# 24_Peripherals.net
KiCad netlist of a schematic drawn in Altium Designer
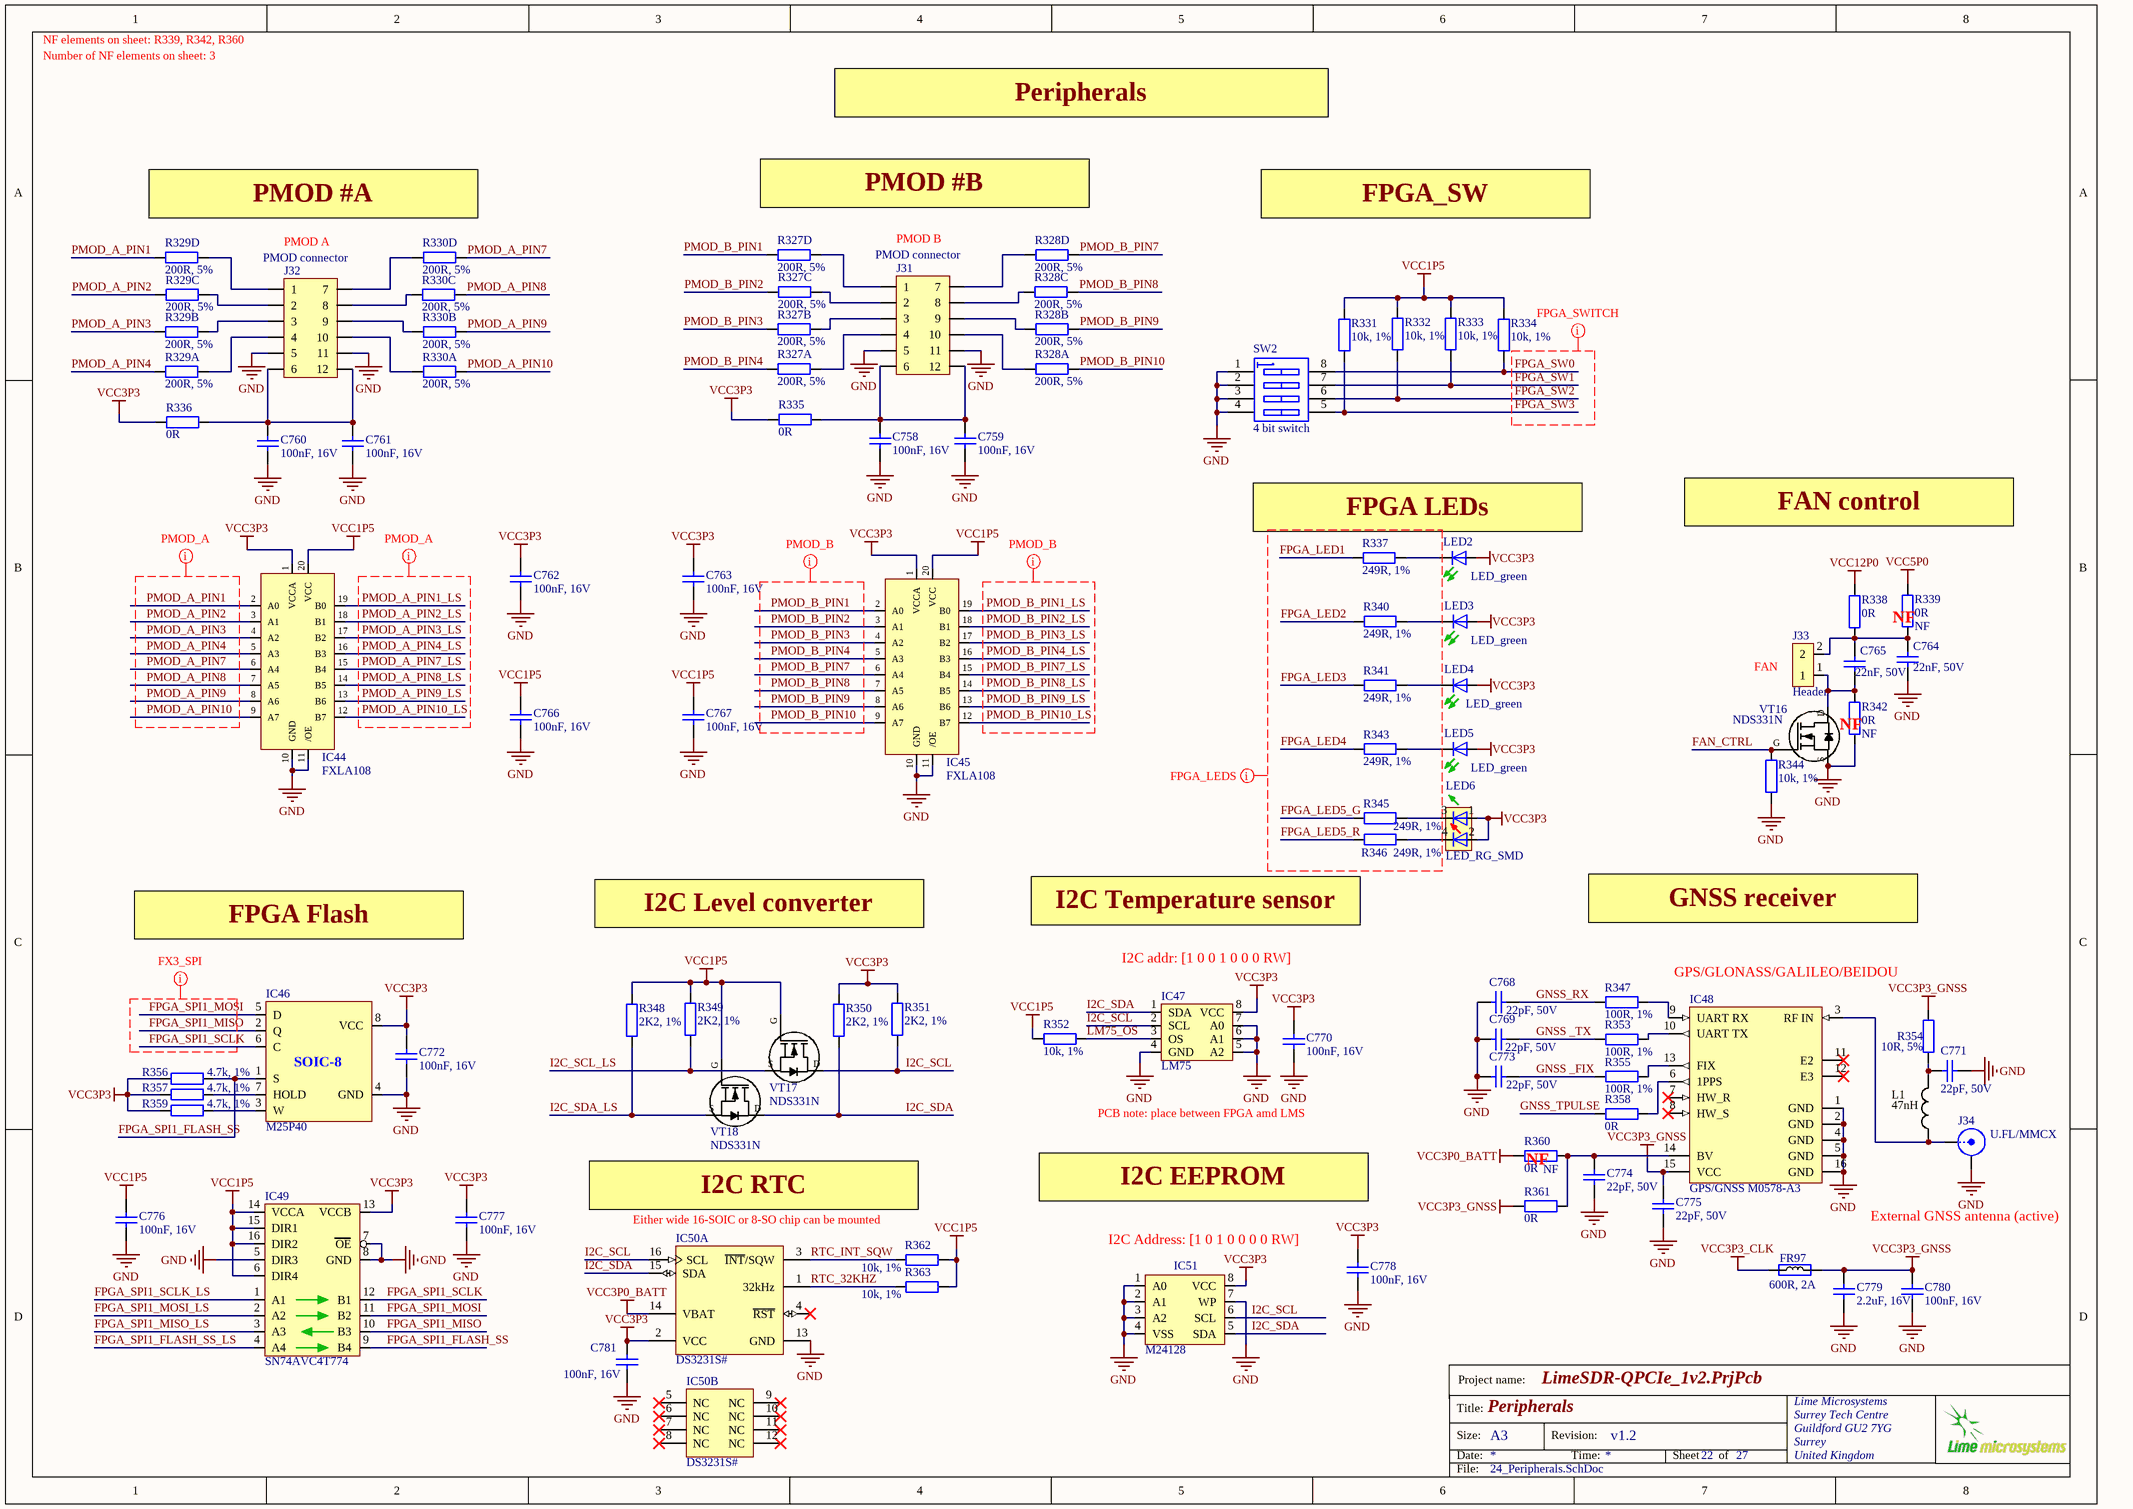
[diagram p0: 24_Peripherals.SchDoc]

(export (version "E")
  (design (tool "Eeschema 10.0.6"))
  (components
    (comp (ref "C758")
      (value "100nF, 16V")
      (footprint "CAP0402")
      (fields
        (field (name "TOLERANCE") "10 %")
        (field (name "MANUFACTURER") "Murata Electronics")
        (field (name "MANUFACTURER PART NUMBER") "GRM155R71C104KA88D")
      )
      (libsource (lib "LimeFPGAboard_schLib") (part "Cap_0603"))
    )
    (comp (ref "C759")
      (value "100nF, 16V")
      (footprint "CAP0402")
      (fields
        (field (name "TOLERANCE") "10 %")
        (field (name "MANUFACTURER") "Murata Electronics")
        (field (name "MANUFACTURER PART NUMBER") "GRM155R71C104KA88D")
      )
      (libsource (lib "LimeFPGAboard_schLib") (part "Cap_0603"))
    )
    (comp (ref "C760")
      (value "100nF, 16V")
      (footprint "CAP0402")
      (fields
        (field (name "TOLERANCE") "10 %")
        (field (name "MANUFACTURER") "Murata Electronics")
        (field (name "MANUFACTURER PART NUMBER") "GRM155R71C104KA88D")
      )
      (libsource (lib "LimeFPGAboard_schLib") (part "Cap_0603"))
    )
    (comp (ref "C761")
      (value "100nF, 16V")
      (footprint "CAP0402")
      (fields
        (field (name "TOLERANCE") "10 %")
        (field (name "MANUFACTURER") "Murata Electronics")
        (field (name "MANUFACTURER PART NUMBER") "GRM155R71C104KA88D")
      )
      (libsource (lib "LimeFPGAboard_schLib") (part "Cap_0603"))
    )
    (comp (ref "C762")
      (value "100nF, 16V")
      (footprint "CAP0402")
      (fields
        (field (name "TOLERANCE") "10 %")
        (field (name "MANUFACTURER") "Murata Electronics")
        (field (name "MANUFACTURER PART NUMBER") "GRM155R71C104KA88D")
      )
      (libsource (lib "LimeFPGAboard_schLib") (part "Cap_0603"))
    )
    (comp (ref "C763")
      (value "100nF, 16V")
      (footprint "CAP0402")
      (fields
        (field (name "TOLERANCE") "10 %")
        (field (name "MANUFACTURER") "Murata Electronics")
        (field (name "MANUFACTURER PART NUMBER") "GRM155R71C104KA88D")
      )
      (libsource (lib "LimeFPGAboard_schLib") (part "Cap_0603"))
    )
    (comp (ref "C764")
      (value "22nF, 50V")
      (footprint "CAP0402")
      (fields (field (name "TOLERANCE") "±10%") (field (name "MANUFACTURER") "Kemet"))
      (libsource (lib "LimeMicroAltiumLib_schLib") (part "Cap_0402"))
    )
    (comp (ref "C765")
      (value "22nF, 50V")
      (footprint "CAP0402")
      (fields (field (name "TOLERANCE") "±10%") (field (name "MANUFACTURER") "Kemet"))
      (libsource (lib "LimeMicroAltiumLib_schLib") (part "Cap_0402"))
    )
    (comp (ref "C766")
      (value "100nF, 16V")
      (footprint "CAP0402")
      (fields
        (field (name "TOLERANCE") "10 %")
        (field (name "MANUFACTURER") "Murata Electronics")
        (field (name "MANUFACTURER PART NUMBER") "GRM155R71C104KA88D")
      )
      (libsource (lib "LimeFPGAboard_schLib") (part "Cap_0603"))
    )
    (comp (ref "C767")
      (value "100nF, 16V")
      (footprint "CAP0402")
      (fields
        (field (name "TOLERANCE") "10 %")
        (field (name "MANUFACTURER") "Murata Electronics")
        (field (name "MANUFACTURER PART NUMBER") "GRM155R71C104KA88D")
      )
      (libsource (lib "LimeFPGAboard_schLib") (part "Cap_0603"))
    )
    (comp (ref "C768")
      (value "22pF, 50V")
      (footprint "CAP0402")
      (fields (field (name "TOLERANCE") "±5%") (field (name "MANUFACTURER") "Yageo"))
      (libsource (lib "LimeMicroAltiumLib_schLib") (part "Cap_0402"))
    )
    (comp (ref "C769")
      (value "22pF, 50V")
      (footprint "CAP0402")
      (fields (field (name "TOLERANCE") "±5%") (field (name "MANUFACTURER") "Yageo"))
      (libsource (lib "LimeMicroAltiumLib_schLib") (part "Cap_0402"))
    )
    (comp (ref "C770")
      (value "100nF, 16V")
      (footprint "CAP0402")
      (fields
        (field (name "TOLERANCE") "10 %")
        (field (name "MANUFACTURER") "Murata Electronics")
        (field (name "MANUFACTURER PART NUMBER") "GRM155R71C104KA88D")
      )
      (libsource (lib "LimeFPGAboard_schLib") (part "Cap_0603"))
    )
    (comp (ref "C771")
      (value "22pF, 50V")
      (footprint "CAP0402")
      (fields (field (name "TOLERANCE") "±5%") (field (name "MANUFACTURER") "Yageo"))
      (libsource (lib "LimeMicroAltiumLib_schLib") (part "Cap_0402"))
    )
    (comp (ref "C772")
      (value "100nF, 16V")
      (footprint "CAP0402")
      (fields
        (field (name "TOLERANCE") "10 %")
        (field (name "MANUFACTURER") "Murata Electronics")
        (field (name "MANUFACTURER PART NUMBER") "GRM155R71C104KA88D")
      )
      (libsource (lib "LimeFPGAboard_schLib") (part "Cap_0603"))
    )
    (comp (ref "C773")
      (value "22pF, 50V")
      (footprint "CAP0402")
      (fields (field (name "TOLERANCE") "±5%") (field (name "MANUFACTURER") "Yageo"))
      (libsource (lib "LimeMicroAltiumLib_schLib") (part "Cap_0402"))
    )
    (comp (ref "C774")
      (value "22pF, 50V")
      (footprint "CAP0402")
      (fields (field (name "TOLERANCE") "±5%") (field (name "MANUFACTURER") "Yageo"))
      (libsource (lib "LimeMicroAltiumLib_schLib") (part "Cap_0402"))
    )
    (comp (ref "C775")
      (value "22pF, 50V")
      (footprint "CAP0402")
      (fields (field (name "TOLERANCE") "±5%") (field (name "MANUFACTURER") "Yageo"))
      (libsource (lib "LimeMicroAltiumLib_schLib") (part "Cap_0402"))
    )
    (comp (ref "C776")
      (value "100nF, 16V")
      (footprint "CAP0402")
      (fields
        (field (name "TOLERANCE") "10 %")
        (field (name "MANUFACTURER") "Murata Electronics")
        (field (name "MANUFACTURER PART NUMBER") "GRM155R71C104KA88D")
      )
      (libsource (lib "LimeFPGAboard_schLib") (part "Cap_0603"))
    )
    (comp (ref "C777")
      (value "100nF, 16V")
      (footprint "CAP0402")
      (fields
        (field (name "TOLERANCE") "10 %")
        (field (name "MANUFACTURER") "Murata Electronics")
        (field (name "MANUFACTURER PART NUMBER") "GRM155R71C104KA88D")
      )
      (libsource (lib "LimeFPGAboard_schLib") (part "Cap_0603"))
    )
    (comp (ref "C778")
      (value "100nF, 16V")
      (footprint "CAP0402")
      (fields
        (field (name "TOLERANCE") "10 %")
        (field (name "MANUFACTURER") "Murata Electronics")
        (field (name "MANUFACTURER PART NUMBER") "GRM155R71C104KA88D")
      )
      (libsource (lib "LimeFPGAboard_schLib") (part "Cap_0603"))
    )
    (comp (ref "C779")
      (value "2.2uF, 16V")
      (footprint "CAP0402")
      (description "CAP CER 2.2UF 16V 10% X5R 0402")
      (fields (field (name "MANUFACTURER") "TDK Corporation") (field (name "TOLERANCE") "±20%"))
      (libsource (lib "LimeMicroAltiumLib_schLib") (part "Cap_0402"))
    )
    (comp (ref "C780")
      (value "100nF, 16V")
      (footprint "CAP0402")
      (fields
        (field (name "MANUFACTURER") "Murata Electronics")
        (field (name "TOLERANCE") "10 %")
        (field (name "MANUFACTURER PART NUMBER") "GRM155R71C104KA88D")
      )
      (libsource (lib "LimeMicroAltiumLib_schLib") (part "Cap_0402"))
    )
    (comp (ref "C781")
      (value "100nF, 16V")
      (footprint "CAP0402")
      (fields
        (field (name "MANUFACTURER") "Murata Electronics")
        (field (name "TOLERANCE") "10 %")
        (field (name "MANUFACTURER PART NUMBER") "GRM155R71C104KA88D")
      )
      (libsource (lib "LimeMicroAltiumLib_schLib") (part "Cap_0402"))
    )
    (comp (ref "FR97")
      (value "600R, 2A")
      (footprint "RES0805")
      (fields (field (name "MANUFACTURER") "TDK"))
      (libsource (lib "LimeMicroAltiumLib_schLib") (part "Ferrite"))
    )
    (comp (ref "IC44")
      (value "FXLA108")
      (footprint "FXLA108")
      (fields (field (name "MANUFACTURER") "Fairchild Semiconductor"))
      (libsource (lib "LimeFPGAboard_schLib") (part "FXLA108"))
    )
    (comp (ref "IC45")
      (value "FXLA108")
      (footprint "FXLA108")
      (fields (field (name "MANUFACTURER") "Fairchild Semiconductor"))
      (libsource (lib "LimeFPGAboard_schLib") (part "FXLA108"))
    )
    (comp (ref "IC46")
      (value "M25P40")
      (footprint "M25P40-VMN6TPB_SO8N")
      (fields (field (name "MANUFACTURER") "Micron Technology Inc"))
      (libsource (lib "LimeFPGAboard_schLib") (part "M25P40"))
    )
    (comp (ref "IC47")
      (value "LM75")
      (footprint "HWSON8_LM75")
      (fields
        (field (name "MANUFACTURER") "NXP Semiconductors")
        (field (name "MANUFACTURER PART NUMBER") "LM75BTP,147")
      )
      (libsource (lib "LimeMicroAltiumLib_schLib") (part "LM75"))
    )
    (comp (ref "IC48")
      (value "GPS/GNSS M0578-A3")
      (footprint "M10578-A3")
      (fields (field (name "MANUFACTURER") "Antenova"))
      (libsource (lib "LimeMicroAltiumLib_schLib") (part "M10578-A3_GPS_GNSS"))
    )
    (comp (ref "IC49")
      (value "SN74AVC4T774")
      (footprint "SN74AVC4T774")
      (fields (field (name "MANUFACTURER") "Texas Instruments"))
      (libsource (lib "LimeMicroAltiumLib_schLib") (part "SN74AVC4T774"))
    )
    (comp (ref "IC50")
      (value "DS3231S#")
      (footprint "DS3231S#_SOIC16_SOIC8")
      (fields (field (name "MANUFACTURER") "MAXIM INTEGRATED PRODUCTS"))
      (libsource (lib "LimeMicroAltiumLib_schLib") (part "DS3231S#"))
    )
    (comp (ref "IC51")
      (value "M24128")
      (footprint "24FC512")
      (fields (field (name "MANUFACTURER") "STMicroelectronics"))
      (libsource (lib "LimeMicroAltiumLib_schLib") (part "24FC64F"))
    )
    (comp (ref "J31")
      (value "PMOD connector")
      (footprint "PMODconn_right_angle_TH")
      (description "Header, 4-Pin, Dual row")
      (fields (field (name "MANUFACTURER") "Sullins Connector Solutions"))
      (libsource (lib "LimeMicroAltiumLib_schLib") (part "PMOD_connector"))
    )
    (comp (ref "J32")
      (value "PMOD connector")
      (footprint "PMODconn_right_angle_TH")
      (description "Header, 4-Pin, Dual row")
      (fields (field (name "MANUFACTURER") "Sullins Connector Solutions"))
      (libsource (lib "LimeMicroAltiumLib_schLib") (part "PMOD_connector"))
    )
    (comp (ref "J33")
      (value "Header")
      (footprint "HDR_1x2")
      (fields (field (name "MANUFACTURER") "3M"))
      (libsource (lib "LimeFPGAboard_schLib") (part "Jumper"))
    )
    (comp (ref "J34")
      (value "U.FL/MMCX")
      (footprint "MMCX_UFL_conn_u")
      (description "CONN UMC RCPT STR 50 OHM SMD")
      (fields (field (name "MANUFACTURER") "Molex, LLC"))
      (libsource (lib "LimeMicroAltiumLib_schLib") (part "RF_IF_connector"))
    )
    (comp (ref "L1")
      (value "47nH")
      (footprint "RES0402")
      (fields
        (field (name "MANUFACTURER") "COILCRAFT")
        (field (name "MANUFACTURER PART NUMBER") "0402HP-47NXJLU")
      )
      (libsource (lib "LimeMicroAltiumLib_schLib") (part "Inductor_0603"))
    )
    (comp (ref "LED2")
      (value "LED_green")
      (footprint "LED-0603-GREEN")
      (fields
        (field (name "MANUFACTURER") "Avago Technologies US Inc.")
        (field (name "MANUFACTURER_1") "Broadcom Limited")
      )
      (libsource (lib "LimeMicroAltiumLib_schLib") (part "LED_green"))
    )
    (comp (ref "LED3")
      (value "LED_green")
      (footprint "LED-0603-GREEN")
      (fields
        (field (name "MANUFACTURER") "Avago Technologies US Inc.")
        (field (name "MANUFACTURER_1") "Broadcom Limited")
      )
      (libsource (lib "LimeMicroAltiumLib_schLib") (part "LED_green"))
    )
    (comp (ref "LED4")
      (value "LED_green")
      (footprint "LED-0603-GREEN")
      (fields
        (field (name "MANUFACTURER") "Avago Technologies US Inc.")
        (field (name "MANUFACTURER_1") "Broadcom Limited")
      )
      (libsource (lib "LimeMicroAltiumLib_schLib") (part "LED_green"))
    )
    (comp (ref "LED5")
      (value "LED_green")
      (footprint "LED-0603-GREEN")
      (fields
        (field (name "MANUFACTURER") "Avago Technologies US Inc.")
        (field (name "MANUFACTURER_1") "Broadcom Limited")
      )
      (libsource (lib "LimeMicroAltiumLib_schLib") (part "LED_green"))
    )
    (comp (ref "LED6")
      (value "LED_RG_SMD")
      (footprint "LED-2x0603")
      (fields (field (name "MANUFACTURER") "Avago Technologies US Inc."))
      (libsource (lib "LimeMicroAltiumLib_schLib") (part "LED_green_red_SMD"))
    )
    (comp (ref "R327")
      (value "200R, 5%")
      (footprint "ChipResistorArray")
      (fields (field (name "MANUFACTURER") "Vishay Dale") (field (name "TOLERANCE") "±5%"))
      (libsource (lib "altium-import") (part "root_0_ResArray_0802_"))
    )
    (comp (ref "R328")
      (value "200R, 5%")
      (footprint "ChipResistorArray")
      (fields (field (name "MANUFACTURER") "Vishay Dale") (field (name "TOLERANCE") "±5%"))
      (libsource (lib "altium-import") (part "root_0_mirrored_ResArray_0802_"))
    )
    (comp (ref "R329")
      (value "200R, 5%")
      (footprint "ChipResistorArray")
      (fields (field (name "MANUFACTURER") "Vishay Dale") (field (name "TOLERANCE") "±5%"))
      (libsource (lib "altium-import") (part "root_0_ResArray_0802_"))
    )
    (comp (ref "R330")
      (value "200R, 5%")
      (footprint "ChipResistorArray")
      (fields (field (name "MANUFACTURER") "Vishay Dale") (field (name "TOLERANCE") "±5%"))
      (libsource (lib "altium-import") (part "root_0_mirrored_ResArray_0802_"))
    )
    (comp (ref "R331")
      (value "10k, 1%")
      (footprint "RES0402")
      (fields (field (name "MANUFACTURER") "Yageo") (field (name "TOLERANCE") "±1%"))
      (libsource (lib "LimeMicroAltiumLib_schLib") (part "Res_0402"))
    )
    (comp (ref "R332")
      (value "10k, 1%")
      (footprint "RES0402")
      (fields (field (name "MANUFACTURER") "Yageo") (field (name "TOLERANCE") "±1%"))
      (libsource (lib "LimeMicroAltiumLib_schLib") (part "Res_0402"))
    )
    (comp (ref "R333")
      (value "10k, 1%")
      (footprint "RES0402")
      (fields (field (name "MANUFACTURER") "Yageo") (field (name "TOLERANCE") "±1%"))
      (libsource (lib "LimeMicroAltiumLib_schLib") (part "Res_0402"))
    )
    (comp (ref "R334")
      (value "10k, 1%")
      (footprint "RES0402")
      (fields (field (name "MANUFACTURER") "Yageo") (field (name "TOLERANCE") "±1%"))
      (libsource (lib "LimeMicroAltiumLib_schLib") (part "Res_0402"))
    )
    (comp (ref "R335")
      (value "0R")
      (footprint "RES0402")
      (fields (field (name "MANUFACTURER") "Yageo") (field (name "TOLERANCE") "Jumper"))
      (libsource (lib "LimeMicroAltiumLib_schLib") (part "Res_0402"))
    )
    (comp (ref "R336")
      (value "0R")
      (footprint "RES0402")
      (fields (field (name "MANUFACTURER") "Yageo") (field (name "TOLERANCE") "Jumper"))
      (libsource (lib "LimeMicroAltiumLib_schLib") (part "Res_0402"))
    )
    (comp (ref "R337")
      (value "249R, 1%")
      (footprint "RES0402")
      (fields (field (name "MANUFACTURER") "Stackpole Electronics Inc") (field (name "TOLERANCE") "±1%"))
      (libsource (lib "LimeMicroAltiumLib_schLib") (part "Res_0402"))
    )
    (comp (ref "R338")
      (value "0R")
      (footprint "RES0402")
      (fields (field (name "MANUFACTURER") "Yageo") (field (name "TOLERANCE") "Jumper"))
      (libsource (lib "LimeMicroAltiumLib_schLib") (part "Res_0402"))
    )
    (comp (ref "R339")
      (value "0R")
      (footprint "RES0402")
      (fields
        (field (name "ASSEMBLY INFO") "NF")
        (field (name "MANUFACTURER") "Yageo")
        (field (name "TOLERANCE") "Jumper")
      )
      (libsource (lib "LimeMicroAltiumLib_schLib") (part "Res_0402"))
    )
    (comp (ref "R340")
      (value "249R, 1%")
      (footprint "RES0402")
      (fields (field (name "MANUFACTURER") "Stackpole Electronics Inc") (field (name "TOLERANCE") "±1%"))
      (libsource (lib "LimeMicroAltiumLib_schLib") (part "Res_0402"))
    )
    (comp (ref "R341")
      (value "249R, 1%")
      (footprint "RES0402")
      (fields (field (name "MANUFACTURER") "Stackpole Electronics Inc") (field (name "TOLERANCE") "±1%"))
      (libsource (lib "LimeMicroAltiumLib_schLib") (part "Res_0402"))
    )
    (comp (ref "R342")
      (value "0R")
      (footprint "RES0402")
      (fields
        (field (name "ASSEMBLY INFO") "NF")
        (field (name "MANUFACTURER") "Yageo")
        (field (name "TOLERANCE") "Jumper")
      )
      (libsource (lib "LimeMicroAltiumLib_schLib") (part "Res_0402"))
    )
    (comp (ref "R343")
      (value "249R, 1%")
      (footprint "RES0402")
      (fields (field (name "MANUFACTURER") "Stackpole Electronics Inc") (field (name "TOLERANCE") "±1%"))
      (libsource (lib "LimeMicroAltiumLib_schLib") (part "Res_0402"))
    )
    (comp (ref "R344")
      (value "10k, 1%")
      (footprint "RES0402")
      (fields (field (name "MANUFACTURER") "Yageo") (field (name "TOLERANCE") "±1%"))
      (libsource (lib "LimeMicroAltiumLib_schLib") (part "Res_0402"))
    )
    (comp (ref "R345")
      (value "249R, 1%")
      (footprint "RES0402")
      (fields (field (name "MANUFACTURER") "Stackpole Electronics Inc") (field (name "TOLERANCE") "±1%"))
      (libsource (lib "LimeMicroAltiumLib_schLib") (part "Res_0402"))
    )
    (comp (ref "R346")
      (value "249R, 1%")
      (footprint "RES0402")
      (fields (field (name "MANUFACTURER") "Stackpole Electronics Inc") (field (name "TOLERANCE") "±1%"))
      (libsource (lib "LimeMicroAltiumLib_schLib") (part "Res_0402"))
    )
    (comp (ref "R347")
      (value "100R, 1%")
      (footprint "RES0402")
      (fields (field (name "TOLERANCE") "±1%") (field (name "MANUFACTURER") "Stackpole Electronics Inc."))
      (libsource (lib "LimeFPGAboard_schLib") (part "Res_0402"))
    )
    (comp (ref "R348")
      (value "2K2, 1%")
      (footprint "RES0402")
      (fields (field (name "TOLERANCE") "±1%"))
      (libsource (lib "LimeFPGAboard_schLib") (part "Res_0402"))
    )
    (comp (ref "R349")
      (value "2K2, 1%")
      (footprint "RES0402")
      (fields (field (name "TOLERANCE") "±1%"))
      (libsource (lib "LimeFPGAboard_schLib") (part "Res_0402"))
    )
    (comp (ref "R350")
      (value "2K2, 1%")
      (footprint "RES0402")
      (fields (field (name "TOLERANCE") "±1%"))
      (libsource (lib "LimeFPGAboard_schLib") (part "Res_0402"))
    )
    (comp (ref "R351")
      (value "2K2, 1%")
      (footprint "RES0402")
      (fields (field (name "TOLERANCE") "±1%"))
      (libsource (lib "LimeFPGAboard_schLib") (part "Res_0402"))
    )
    (comp (ref "R352")
      (value "10k, 1%")
      (footprint "RES0402")
      (fields (field (name "MANUFACTURER") "Yageo") (field (name "TOLERANCE") "±1%"))
      (libsource (lib "LimeMicroAltiumLib_schLib") (part "Res_0402"))
    )
    (comp (ref "R353")
      (value "100R, 1%")
      (footprint "RES0402")
      (fields (field (name "TOLERANCE") "±1%") (field (name "MANUFACTURER") "Stackpole Electronics Inc."))
      (libsource (lib "LimeFPGAboard_schLib") (part "Res_0402"))
    )
    (comp (ref "R354")
      (value "10R, 5%")
      (footprint "RES0402")
      (fields (field (name "TOLERANCE") "±5%") (field (name "MANUFACTURER") "Yageo"))
      (libsource (lib "LimeMicroAltiumLib_schLib") (part "Res_0402"))
    )
    (comp (ref "R355")
      (value "100R, 1%")
      (footprint "RES0402")
      (fields (field (name "TOLERANCE") "±1%") (field (name "MANUFACTURER") "Stackpole Electronics Inc."))
      (libsource (lib "LimeFPGAboard_schLib") (part "Res_0402"))
    )
    (comp (ref "R356")
      (value "4.7k, 1%")
      (footprint "RES0402")
      (fields (field (name "MANUFACTURER") "Yageo") (field (name "TOLERANCE") "±1%"))
      (libsource (lib "LimeMicroAltiumLib_schLib") (part "Res_0402"))
    )
    (comp (ref "R357")
      (value "4.7k, 1%")
      (footprint "RES0402")
      (fields (field (name "MANUFACTURER") "Yageo") (field (name "TOLERANCE") "±1%"))
      (libsource (lib "LimeMicroAltiumLib_schLib") (part "Res_0402"))
    )
    (comp (ref "R358")
      (value "0R")
      (footprint "RES0402")
      (fields (field (name "MANUFACTURER") "Yageo") (field (name "TOLERANCE") "Jumper"))
      (libsource (lib "LimeMicroAltiumLib_schLib") (part "Res_0402"))
    )
    (comp (ref "R359")
      (value "4.7k, 1%")
      (footprint "RES0402")
      (fields (field (name "MANUFACTURER") "Yageo") (field (name "TOLERANCE") "±1%"))
      (libsource (lib "LimeMicroAltiumLib_schLib") (part "Res_0402"))
    )
    (comp (ref "R360")
      (value "0R")
      (footprint "RES0402_v2")
      (fields
        (field (name "ASSEMBLY INFO") "NF")
        (field (name "MANUFACTURER") "Yageo")
        (field (name "TOLERANCE") "Jumper")
      )
      (libsource (lib "LimeMicroAltiumLib_schLib") (part "Res_0402"))
    )
    (comp (ref "R361")
      (value "0R")
      (footprint "RES0402")
      (fields (field (name "MANUFACTURER") "Yageo") (field (name "TOLERANCE") "Jumper"))
      (libsource (lib "LimeMicroAltiumLib_schLib") (part "Res_0402"))
    )
    (comp (ref "R362")
      (value "10k, 1%")
      (footprint "RES0402")
      (fields (field (name "MANUFACTURER") "Yageo") (field (name "TOLERANCE") "±1%"))
      (libsource (lib "LimeMicroAltiumLib_schLib") (part "Res_0402"))
    )
    (comp (ref "R363")
      (value "10k, 1%")
      (footprint "RES0402")
      (fields (field (name "MANUFACTURER") "Yageo") (field (name "TOLERANCE") "±1%"))
      (libsource (lib "LimeMicroAltiumLib_schLib") (part "Res_0402"))
    )
    (comp (ref "SW2")
      (value "4 bit switch")
      (footprint "SW_4WAY_SMD_1P27")
      (fields (field (name "MANUFACTURER") "Omron Electronics Inc-EMC Div"))
      (libsource (lib "LimeMicroAltiumLib_schLib") (part "SW_SM_4bit"))
    )
    (comp (ref "VT16")
      (value "NDS331N")
      (footprint "SOT23-3")
      (fields (field (name "MANUFACTURER") "Fairchild Semiconductor"))
      (libsource (lib "LimeFPGAboard_schLib") (part "NDS331N"))
    )
    (comp (ref "VT17")
      (value "NDS331N")
      (footprint "SOT23-3")
      (fields (field (name "MANUFACTURER") "Fairchild Semiconductor"))
      (libsource (lib "LimeFPGAboard_schLib") (part "NDS331N"))
    )
    (comp (ref "VT18")
      (value "NDS331N")
      (footprint "SOT23-3")
      (fields (field (name "MANUFACTURER") "Fairchild Semiconductor"))
      (libsource (lib "LimeFPGAboard_schLib") (part "NDS331N"))
    )
  )
  (nets
    (net (code "1") (name "/FAN_CTRL") (class "Default")
      (node (ref "R344") (pin "1") (pinfunction "1_1") (pintype "passive"))
      (node (ref "VT16") (pin "G") (pinfunction "G_G") (pintype "passive"))
    )
    (net (code "2") (name "/FPGA_LED1") (class "Default")
      (node (ref "R337") (pin "1") (pinfunction "1_1") (pintype "passive"))
    )
    (net (code "3") (name "/FPGA_LED2") (class "Default")
      (node (ref "R340") (pin "1") (pinfunction "1_1") (pintype "passive"))
    )
    (net (code "4") (name "/FPGA_LED3") (class "Default")
      (node (ref "R341") (pin "1") (pinfunction "1_1") (pintype "passive"))
    )
    (net (code "5") (name "/FPGA_LED4") (class "Default")
      (node (ref "R343") (pin "1") (pinfunction "1_1") (pintype "passive"))
    )
    (net (code "6") (name "/FPGA_LED5_G") (class "Default")
      (node (ref "R345") (pin "1") (pinfunction "1_1") (pintype "passive"))
    )
    (net (code "7") (name "/FPGA_LED5_R") (class "Default")
      (node (ref "R346") (pin "1") (pinfunction "1_1") (pintype "passive"))
    )
    (net (code "8") (name "/FPGA_SPI1_FLASH_SS") (class "Default")
      (node (ref "IC46") (pin "1") (pinfunction "S_1") (pintype "passive"))
      (node (ref "IC49") (pin "9") (pinfunction "B4_9") (pintype "passive"))
      (node (ref "R356") (pin "1") (pinfunction "1_1") (pintype "passive"))
    )
    (net (code "9") (name "/FPGA_SPI1_FLASH_SS_LS") (class "Default")
      (node (ref "IC49") (pin "4") (pinfunction "A4_4") (pintype "passive"))
    )
    (net (code "10") (name "/FPGA_SPI1_MISO") (class "Default")
      (node (ref "IC46") (pin "2") (pinfunction "Q_2") (pintype "passive"))
      (node (ref "IC49") (pin "10") (pinfunction "B3_10") (pintype "passive"))
    )
    (net (code "11") (name "/FPGA_SPI1_MISO_LS") (class "Default")
      (node (ref "IC49") (pin "3") (pinfunction "A3_3") (pintype "passive"))
    )
    (net (code "12") (name "/FPGA_SPI1_MOSI") (class "Default")
      (node (ref "IC46") (pin "5") (pinfunction "D_5") (pintype "passive"))
      (node (ref "IC49") (pin "11") (pinfunction "B2_11") (pintype "passive"))
    )
    (net (code "13") (name "/FPGA_SPI1_MOSI_LS") (class "Default")
      (node (ref "IC49") (pin "2") (pinfunction "A2_2") (pintype "passive"))
    )
    (net (code "14") (name "/FPGA_SPI1_SCLK") (class "Default")
      (node (ref "IC46") (pin "6") (pinfunction "C_6") (pintype "passive"))
      (node (ref "IC49") (pin "12") (pinfunction "B1_12") (pintype "passive"))
    )
    (net (code "15") (name "/FPGA_SPI1_SCLK_LS") (class "Default")
      (node (ref "IC49") (pin "1") (pinfunction "A1_1") (pintype "passive"))
    )
    (net (code "16") (name "/FPGA_SW0") (class "Default")
      (node (ref "R334") (pin "2") (pinfunction "2_2") (pintype "passive"))
      (node (ref "SW2") (pin "8") (pinfunction "B1_8") (pintype "passive"))
    )
    (net (code "17") (name "/FPGA_SW1") (class "Default")
      (node (ref "R333") (pin "2") (pinfunction "2_2") (pintype "passive"))
      (node (ref "SW2") (pin "7") (pinfunction "B2_7") (pintype "passive"))
    )
    (net (code "18") (name "/FPGA_SW2") (class "Default")
      (node (ref "R332") (pin "2") (pinfunction "2_2") (pintype "passive"))
      (node (ref "SW2") (pin "6") (pinfunction "B3_6") (pintype "passive"))
    )
    (net (code "19") (name "/FPGA_SW3") (class "Default")
      (node (ref "R331") (pin "2") (pinfunction "2_2") (pintype "passive"))
      (node (ref "SW2") (pin "5") (pinfunction "B4_5") (pintype "passive"))
    )
    (net (code "20") (name "/GNSS _FIX") (class "Default")
      (node (ref "C773") (pin "1") (pinfunction "1_1") (pintype "passive"))
      (node (ref "R355") (pin "2") (pinfunction "2_2") (pintype "passive"))
    )
    (net (code "21") (name "/GNSS _TX") (class "Default")
      (node (ref "C769") (pin "1") (pinfunction "1_1") (pintype "passive"))
      (node (ref "R353") (pin "2") (pinfunction "2_2") (pintype "passive"))
    )
    (net (code "22") (name "/GNSS_RX") (class "Default")
      (node (ref "C768") (pin "1") (pinfunction "1_1") (pintype "passive"))
      (node (ref "R347") (pin "2") (pinfunction "2_2") (pintype "passive"))
    )
    (net (code "23") (name "/GNSS_TPULSE") (class "Default")
      (node (ref "R358") (pin "2") (pinfunction "2_2") (pintype "passive"))
    )
    (net (code "24") (name "/I2C_SCL") (class "Default")
      (node (ref "IC47") (pin "2") (pinfunction "SCL_2") (pintype "passive"))
      (node (ref "IC50") (pin "16") (pinfunction "SCL_16") (pintype "input"))
      (node (ref "IC51") (pin "6") (pinfunction "SCL_6") (pintype "passive"))
      (node (ref "R351") (pin "2") (pinfunction "2_2") (pintype "passive"))
      (node (ref "VT17") (pin "D") (pinfunction "D_D") (pintype "passive"))
    )
    (net (code "25") (name "/I2C_SCL_LS") (class "Default")
      (node (ref "R349") (pin "2") (pinfunction "2_2") (pintype "passive"))
      (node (ref "VT17") (pin "S") (pinfunction "S_S") (pintype "passive"))
    )
    (net (code "26") (name "/I2C_SDA") (class "Default")
      (node (ref "IC47") (pin "1") (pinfunction "SDA_1") (pintype "passive"))
      (node (ref "IC50") (pin "15") (pinfunction "SDA_15") (pintype "bidirectional"))
      (node (ref "IC51") (pin "5") (pinfunction "SDA_5") (pintype "passive"))
      (node (ref "R350") (pin "2") (pinfunction "2_2") (pintype "passive"))
      (node (ref "VT18") (pin "D") (pinfunction "D_D") (pintype "passive"))
    )
    (net (code "27") (name "/I2C_SDA_LS") (class "Default")
      (node (ref "R348") (pin "2") (pinfunction "2_2") (pintype "passive"))
      (node (ref "VT18") (pin "S") (pinfunction "S_S") (pintype "passive"))
    )
    (net (code "28") (name "/LM75_OS") (class "Default")
      (node (ref "IC47") (pin "3") (pinfunction "OS_3") (pintype "passive"))
      (node (ref "R352") (pin "1") (pinfunction "1_1") (pintype "passive"))
    )
    (net (code "29") (name "/PMOD_A_PIN1") (class "Default")
      (node (ref "IC44") (pin "2") (pinfunction "A0_2") (pintype "passive"))
      (node (ref "R329") (pin "7") (pinfunction "7_7") (pintype "passive"))
    )
    (net (code "30") (name "/PMOD_A_PIN1_LS") (class "Default")
      (node (ref "IC44") (pin "19") (pinfunction "B0_19") (pintype "passive"))
    )
    (net (code "31") (name "/PMOD_A_PIN2") (class "Default")
      (node (ref "IC44") (pin "3") (pinfunction "A1_3") (pintype "passive"))
      (node (ref "R329") (pin "5") (pinfunction "5_5") (pintype "passive"))
    )
    (net (code "32") (name "/PMOD_A_PIN2_LS") (class "Default")
      (node (ref "IC44") (pin "18") (pinfunction "B1_18") (pintype "passive"))
    )
    (net (code "33") (name "/PMOD_A_PIN3") (class "Default")
      (node (ref "IC44") (pin "4") (pinfunction "A2_4") (pintype "passive"))
      (node (ref "R329") (pin "3") (pinfunction "3_3") (pintype "passive"))
    )
    (net (code "34") (name "/PMOD_A_PIN3_LS") (class "Default")
      (node (ref "IC44") (pin "17") (pinfunction "B2_17") (pintype "passive"))
    )
    (net (code "35") (name "/PMOD_A_PIN4") (class "Default")
      (node (ref "IC44") (pin "5") (pinfunction "A3_5") (pintype "passive"))
      (node (ref "R329") (pin "1") (pinfunction "1_1") (pintype "passive"))
    )
    (net (code "36") (name "/PMOD_A_PIN4_LS") (class "Default")
      (node (ref "IC44") (pin "16") (pinfunction "B3_16") (pintype "passive"))
    )
    (net (code "37") (name "/PMOD_A_PIN7") (class "Default")
      (node (ref "IC44") (pin "6") (pinfunction "A4_6") (pintype "passive"))
      (node (ref "R330") (pin "7") (pinfunction "7_7") (pintype "passive"))
    )
    (net (code "38") (name "/PMOD_A_PIN7_LS") (class "Default")
      (node (ref "IC44") (pin "15") (pinfunction "B4_15") (pintype "passive"))
    )
    (net (code "39") (name "/PMOD_A_PIN8") (class "Default")
      (node (ref "IC44") (pin "7") (pinfunction "A5_7") (pintype "passive"))
      (node (ref "R330") (pin "5") (pinfunction "5_5") (pintype "passive"))
    )
    (net (code "40") (name "/PMOD_A_PIN8_LS") (class "Default")
      (node (ref "IC44") (pin "14") (pinfunction "B5_14") (pintype "passive"))
    )
    (net (code "41") (name "/PMOD_A_PIN9") (class "Default")
      (node (ref "IC44") (pin "8") (pinfunction "A6_8") (pintype "passive"))
      (node (ref "R330") (pin "3") (pinfunction "3_3") (pintype "passive"))
    )
    (net (code "42") (name "/PMOD_A_PIN9_LS") (class "Default")
      (node (ref "IC44") (pin "13") (pinfunction "B6_13") (pintype "passive"))
    )
    (net (code "43") (name "/PMOD_A_PIN10") (class "Default")
      (node (ref "IC44") (pin "9") (pinfunction "A7_9") (pintype "passive"))
      (node (ref "R330") (pin "1") (pinfunction "1_1") (pintype "passive"))
    )
    (net (code "44") (name "/PMOD_A_PIN10_LS") (class "Default")
      (node (ref "IC44") (pin "12") (pinfunction "B7_12") (pintype "passive"))
    )
    (net (code "45") (name "/PMOD_B_PIN1") (class "Default")
      (node (ref "IC45") (pin "2") (pinfunction "A0_2") (pintype "passive"))
      (node (ref "R327") (pin "7") (pinfunction "7_7") (pintype "passive"))
    )
    (net (code "46") (name "/PMOD_B_PIN1_LS") (class "Default")
      (node (ref "IC45") (pin "19") (pinfunction "B0_19") (pintype "passive"))
    )
    (net (code "47") (name "/PMOD_B_PIN2") (class "Default")
      (node (ref "IC45") (pin "3") (pinfunction "A1_3") (pintype "passive"))
      (node (ref "R327") (pin "5") (pinfunction "5_5") (pintype "passive"))
    )
    (net (code "48") (name "/PMOD_B_PIN2_LS") (class "Default")
      (node (ref "IC45") (pin "18") (pinfunction "B1_18") (pintype "passive"))
    )
    (net (code "49") (name "/PMOD_B_PIN3") (class "Default")
      (node (ref "IC45") (pin "4") (pinfunction "A2_4") (pintype "passive"))
      (node (ref "R327") (pin "3") (pinfunction "3_3") (pintype "passive"))
    )
    (net (code "50") (name "/PMOD_B_PIN3_LS") (class "Default")
      (node (ref "IC45") (pin "17") (pinfunction "B2_17") (pintype "passive"))
    )
    (net (code "51") (name "/PMOD_B_PIN4") (class "Default")
      (node (ref "IC45") (pin "5") (pinfunction "A3_5") (pintype "passive"))
      (node (ref "R327") (pin "1") (pinfunction "1_1") (pintype "passive"))
    )
    (net (code "52") (name "/PMOD_B_PIN4_LS") (class "Default")
      (node (ref "IC45") (pin "16") (pinfunction "B3_16") (pintype "passive"))
    )
    (net (code "53") (name "/PMOD_B_PIN7") (class "Default")
      (node (ref "IC45") (pin "6") (pinfunction "A4_6") (pintype "passive"))
      (node (ref "R328") (pin "7") (pinfunction "7_7") (pintype "passive"))
    )
    (net (code "54") (name "/PMOD_B_PIN7_LS") (class "Default")
      (node (ref "IC45") (pin "15") (pinfunction "B4_15") (pintype "passive"))
    )
    (net (code "55") (name "/PMOD_B_PIN8") (class "Default")
      (node (ref "IC45") (pin "7") (pinfunction "A5_7") (pintype "passive"))
      (node (ref "R328") (pin "5") (pinfunction "5_5") (pintype "passive"))
    )
    (net (code "56") (name "/PMOD_B_PIN8_LS") (class "Default")
      (node (ref "IC45") (pin "14") (pinfunction "B5_14") (pintype "passive"))
    )
    (net (code "57") (name "/PMOD_B_PIN9") (class "Default")
      (node (ref "IC45") (pin "8") (pinfunction "A6_8") (pintype "passive"))
      (node (ref "R328") (pin "3") (pinfunction "3_3") (pintype "passive"))
    )
    (net (code "58") (name "/PMOD_B_PIN9_LS") (class "Default")
      (node (ref "IC45") (pin "13") (pinfunction "B6_13") (pintype "passive"))
    )
    (net (code "59") (name "/PMOD_B_PIN10") (class "Default")
      (node (ref "IC45") (pin "9") (pinfunction "A7_9") (pintype "passive"))
      (node (ref "R328") (pin "1") (pinfunction "1_1") (pintype "passive"))
    )
    (net (code "60") (name "/PMOD_B_PIN10_LS") (class "Default")
      (node (ref "IC45") (pin "12") (pinfunction "B7_12") (pintype "passive"))
    )
    (net (code "61") (name "/RTC_32KHZ") (class "Default")
      (node (ref "IC50") (pin "1") (pinfunction "32kHz_1") (pintype "open_collector"))
      (node (ref "R363") (pin "1") (pinfunction "1_1") (pintype "passive"))
    )
    (net (code "62") (name "/RTC_INT_SQW") (class "Default")
      (node (ref "IC50") (pin "3") (pinfunction "~{INT}/SQW_3") (pintype "open_collector"))
      (node (ref "R362") (pin "1") (pinfunction "1_1") (pintype "passive"))
    )
    (net (code "63") (name "GND") (class "Default")
      (node (ref "C758") (pin "2") (pinfunction "2_2") (pintype "passive"))
      (node (ref "C759") (pin "2") (pinfunction "2_2") (pintype "passive"))
      (node (ref "C760") (pin "2") (pinfunction "2_2") (pintype "passive"))
      (node (ref "C761") (pin "2") (pinfunction "2_2") (pintype "passive"))
      (node (ref "C762") (pin "2") (pinfunction "2_2") (pintype "passive"))
      (node (ref "C763") (pin "2") (pinfunction "2_2") (pintype "passive"))
      (node (ref "C764") (pin "2") (pinfunction "2_2") (pintype "passive"))
      (node (ref "C766") (pin "2") (pinfunction "2_2") (pintype "passive"))
      (node (ref "C767") (pin "2") (pinfunction "2_2") (pintype "passive"))
      (node (ref "C768") (pin "2") (pinfunction "2_2") (pintype "passive"))
      (node (ref "C769") (pin "2") (pinfunction "2_2") (pintype "passive"))
      (node (ref "C770") (pin "2") (pinfunction "2_2") (pintype "passive"))
      (node (ref "C771") (pin "1") (pinfunction "1_1") (pintype "passive"))
      (node (ref "C772") (pin "2") (pinfunction "2_2") (pintype "passive"))
      (node (ref "C773") (pin "2") (pinfunction "2_2") (pintype "passive"))
      (node (ref "C774") (pin "1") (pinfunction "1_1") (pintype "passive"))
      (node (ref "C775") (pin "1") (pinfunction "1_1") (pintype "passive"))
      (node (ref "C776") (pin "2") (pinfunction "2_2") (pintype "passive"))
      (node (ref "C777") (pin "2") (pinfunction "2_2") (pintype "passive"))
      (node (ref "C778") (pin "2") (pinfunction "2_2") (pintype "passive"))
      (node (ref "C779") (pin "1") (pinfunction "1_1") (pintype "passive"))
      (node (ref "C780") (pin "1") (pinfunction "1_1") (pintype "passive"))
      (node (ref "C781") (pin "2") (pinfunction "2_2") (pintype "passive"))
      (node (ref "IC44") (pin "10") (pinfunction "GND_10") (pintype "passive"))
      (node (ref "IC44") (pin "11") (pinfunction "/OE_11") (pintype "passive"))
      (node (ref "IC45") (pin "10") (pinfunction "GND_10") (pintype "passive"))
      (node (ref "IC45") (pin "11") (pinfunction "/OE_11") (pintype "passive"))
      (node (ref "IC46") (pin "4") (pinfunction "GND_4") (pintype "passive"))
      (node (ref "IC47") (pin "4") (pinfunction "GND_4") (pintype "passive"))
      (node (ref "IC47") (pin "5") (pinfunction "A2_5") (pintype "passive"))
      (node (ref "IC47") (pin "6") (pinfunction "A1_6") (pintype "passive"))
      (node (ref "IC47") (pin "7") (pinfunction "A0_7") (pintype "passive"))
      (node (ref "IC48") (pin "1") (pinfunction "GND_1") (pintype "passive"))
      (node (ref "IC48") (pin "16") (pinfunction "GND_16") (pintype "passive"))
      (node (ref "IC48") (pin "2") (pinfunction "GND_2") (pintype "passive"))
      (node (ref "IC48") (pin "4") (pinfunction "GND_4") (pintype "passive"))
      (node (ref "IC48") (pin "5") (pinfunction "GND_5") (pintype "passive"))
      (node (ref "IC49") (pin "5") (pinfunction "DIR3_5") (pintype "passive"))
      (node (ref "IC49") (pin "7") (pinfunction "OE_7") (pintype "passive"))
      (node (ref "IC49") (pin "8") (pinfunction "GND_8") (pintype "passive"))
      (node (ref "IC50") (pin "13") (pinfunction "GND_13") (pintype "power_in"))
      (node (ref "IC51") (pin "1") (pinfunction "A0_1") (pintype "passive"))
      (node (ref "IC51") (pin "2") (pinfunction "A1_2") (pintype "passive"))
      (node (ref "IC51") (pin "3") (pinfunction "A2_3") (pintype "passive"))
      (node (ref "IC51") (pin "4") (pinfunction "VSS_4") (pintype "passive"))
      (node (ref "IC51") (pin "7") (pinfunction "WP_7") (pintype "passive"))
      (node (ref "J31") (pin "11") (pinfunction "11_11") (pintype "passive"))
      (node (ref "J31") (pin "5") (pinfunction "5_5") (pintype "passive"))
      (node (ref "J32") (pin "11") (pinfunction "11_11") (pintype "passive"))
      (node (ref "J32") (pin "5") (pinfunction "5_5") (pintype "passive"))
      (node (ref "J34") (pin "2") (pinfunction "Y_2") (pintype "passive"))
      (node (ref "R342") (pin "1") (pinfunction "1_1") (pintype "passive"))
      (node (ref "R344") (pin "2") (pinfunction "2_2") (pintype "passive"))
      (node (ref "SW2") (pin "1") (pinfunction "A1_1") (pintype "passive"))
      (node (ref "SW2") (pin "2") (pinfunction "A2_2") (pintype "passive"))
      (node (ref "SW2") (pin "3") (pinfunction "A3_3") (pintype "passive"))
      (node (ref "SW2") (pin "4") (pinfunction "A4_4") (pintype "passive"))
      (node (ref "VT16") (pin "S") (pinfunction "S_S") (pintype "passive"))
    )
    (net (code "64") (name "Net-(C758-Pad1)") (class "Default")
      (node (ref "C758") (pin "1") (pinfunction "1_1") (pintype "passive"))
      (node (ref "C759") (pin "1") (pinfunction "1_1") (pintype "passive"))
      (node (ref "J31") (pin "12") (pinfunction "12_12") (pintype "passive"))
      (node (ref "J31") (pin "6") (pinfunction "6_6") (pintype "passive"))
      (node (ref "R335") (pin "1") (pinfunction "1_1") (pintype "passive"))
    )
    (net (code "65") (name "Net-(C760-Pad1)") (class "Default")
      (node (ref "C760") (pin "1") (pinfunction "1_1") (pintype "passive"))
      (node (ref "C761") (pin "1") (pinfunction "1_1") (pintype "passive"))
      (node (ref "J32") (pin "12") (pinfunction "12_12") (pintype "passive"))
      (node (ref "J32") (pin "6") (pinfunction "6_6") (pintype "passive"))
      (node (ref "R336") (pin "1") (pinfunction "1_1") (pintype "passive"))
    )
    (net (code "66") (name "Net-(C764-Pad1)") (class "Default")
      (node (ref "C764") (pin "1") (pinfunction "1_1") (pintype "passive"))
      (node (ref "C765") (pin "1") (pinfunction "1_1") (pintype "passive"))
      (node (ref "J33") (pin "2") (pinfunction "2_2") (pintype "passive"))
      (node (ref "R338") (pin "1") (pinfunction "1_1") (pintype "passive"))
      (node (ref "R339") (pin "1") (pinfunction "1_1") (pintype "passive"))
    )
    (net (code "67") (name "Net-(C765-Pad2)") (class "Default")
      (node (ref "C765") (pin "2") (pinfunction "2_2") (pintype "passive"))
      (node (ref "J33") (pin "1") (pinfunction "1_1") (pintype "passive"))
      (node (ref "R342") (pin "2") (pinfunction "2_2") (pintype "passive"))
      (node (ref "VT16") (pin "D") (pinfunction "D_D") (pintype "passive"))
    )
    (net (code "68") (name "Net-(C771-Pad2)") (class "Default")
      (node (ref "C771") (pin "2") (pinfunction "2_2") (pintype "passive"))
      (node (ref "L1") (pin "2") (pinfunction "2_2") (pintype "passive"))
      (node (ref "R354") (pin "2") (pinfunction "2_2") (pintype "passive"))
    )
    (net (code "69") (name "Net-(IC46-HOLD)") (class "Default")
      (node (ref "IC46") (pin "7") (pinfunction "HOLD_7") (pintype "passive"))
      (node (ref "R357") (pin "1") (pinfunction "1_1") (pintype "passive"))
    )
    (net (code "70") (name "Net-(IC46-W)") (class "Default")
      (node (ref "IC46") (pin "3") (pinfunction "W_3") (pintype "passive"))
      (node (ref "R359") (pin "1") (pinfunction "1_1") (pintype "passive"))
    )
    (net (code "71") (name "Net-(IC48-1PPS)") (class "Default")
      (node (ref "IC48") (pin "6") (pinfunction "1PPS_6") (pintype "output"))
      (node (ref "R358") (pin "1") (pinfunction "1_1") (pintype "passive"))
    )
    (net (code "72") (name "Net-(IC48-BV)") (class "Default")
      (node (ref "C774") (pin "2") (pinfunction "2_2") (pintype "passive"))
      (node (ref "IC48") (pin "14") (pinfunction "BV_14") (pintype "power_in"))
      (node (ref "R360") (pin "1") (pinfunction "1_1") (pintype "passive"))
      (node (ref "R361") (pin "1") (pinfunction "1_1") (pintype "passive"))
    )
    (net (code "73") (name "Net-(IC48-FIX)") (class "Default")
      (node (ref "IC48") (pin "13") (pinfunction "FIX_13") (pintype "output"))
      (node (ref "R355") (pin "1") (pinfunction "1_1") (pintype "passive"))
    )
    (net (code "74") (name "Net-(IC48-RF_IN)") (class "Default")
      (node (ref "IC48") (pin "3") (pinfunction "RF_IN_3") (pintype "input"))
      (node (ref "J34") (pin "1") (pinfunction "X_1") (pintype "passive"))
      (node (ref "L1") (pin "1") (pinfunction "1_1") (pintype "passive"))
    )
    (net (code "75") (name "Net-(IC48-UART_RX)") (class "Default")
      (node (ref "IC48") (pin "9") (pinfunction "UART_RX_9") (pintype "input"))
      (node (ref "R347") (pin "1") (pinfunction "1_1") (pintype "passive"))
    )
    (net (code "76") (name "Net-(IC48-UART_TX)") (class "Default")
      (node (ref "IC48") (pin "10") (pinfunction "UART_TX_10") (pintype "output"))
      (node (ref "R353") (pin "1") (pinfunction "1_1") (pintype "passive"))
    )
    (net (code "77") (name "Net-(J31-Pad1)") (class "Default")
      (node (ref "J31") (pin "1") (pinfunction "1_1") (pintype "passive"))
      (node (ref "R327") (pin "8") (pinfunction "8_8") (pintype "passive"))
    )
    (net (code "78") (name "Net-(J31-Pad2)") (class "Default")
      (node (ref "J31") (pin "2") (pinfunction "2_2") (pintype "passive"))
      (node (ref "R327") (pin "6") (pinfunction "6_6") (pintype "passive"))
    )
    (net (code "79") (name "Net-(J31-Pad3)") (class "Default")
      (node (ref "J31") (pin "3") (pinfunction "3_3") (pintype "passive"))
      (node (ref "R327") (pin "4") (pinfunction "4_4") (pintype "passive"))
    )
    (net (code "80") (name "Net-(J31-Pad4)") (class "Default")
      (node (ref "J31") (pin "4") (pinfunction "4_4") (pintype "passive"))
      (node (ref "R327") (pin "2") (pinfunction "2_2") (pintype "passive"))
    )
    (net (code "81") (name "Net-(J31-Pad7)") (class "Default")
      (node (ref "J31") (pin "7") (pinfunction "7_7") (pintype "passive"))
      (node (ref "R328") (pin "8") (pinfunction "8_8") (pintype "passive"))
    )
    (net (code "82") (name "Net-(J31-Pad8)") (class "Default")
      (node (ref "J31") (pin "8") (pinfunction "8_8") (pintype "passive"))
      (node (ref "R328") (pin "6") (pinfunction "6_6") (pintype "passive"))
    )
    (net (code "83") (name "Net-(J31-Pad9)") (class "Default")
      (node (ref "J31") (pin "9") (pinfunction "9_9") (pintype "passive"))
      (node (ref "R328") (pin "4") (pinfunction "4_4") (pintype "passive"))
    )
    (net (code "84") (name "Net-(J31-Pad10)") (class "Default")
      (node (ref "J31") (pin "10") (pinfunction "10_10") (pintype "passive"))
      (node (ref "R328") (pin "2") (pinfunction "2_2") (pintype "passive"))
    )
    (net (code "85") (name "Net-(J32-Pad1)") (class "Default")
      (node (ref "J32") (pin "1") (pinfunction "1_1") (pintype "passive"))
      (node (ref "R329") (pin "8") (pinfunction "8_8") (pintype "passive"))
    )
    (net (code "86") (name "Net-(J32-Pad2)") (class "Default")
      (node (ref "J32") (pin "2") (pinfunction "2_2") (pintype "passive"))
      (node (ref "R329") (pin "6") (pinfunction "6_6") (pintype "passive"))
    )
    (net (code "87") (name "Net-(J32-Pad3)") (class "Default")
      (node (ref "J32") (pin "3") (pinfunction "3_3") (pintype "passive"))
      (node (ref "R329") (pin "4") (pinfunction "4_4") (pintype "passive"))
    )
    (net (code "88") (name "Net-(J32-Pad4)") (class "Default")
      (node (ref "J32") (pin "4") (pinfunction "4_4") (pintype "passive"))
      (node (ref "R329") (pin "2") (pinfunction "2_2") (pintype "passive"))
    )
    (net (code "89") (name "Net-(J32-Pad7)") (class "Default")
      (node (ref "J32") (pin "7") (pinfunction "7_7") (pintype "passive"))
      (node (ref "R330") (pin "8") (pinfunction "8_8") (pintype "passive"))
    )
    (net (code "90") (name "Net-(J32-Pad8)") (class "Default")
      (node (ref "J32") (pin "8") (pinfunction "8_8") (pintype "passive"))
      (node (ref "R330") (pin "6") (pinfunction "6_6") (pintype "passive"))
    )
    (net (code "91") (name "Net-(J32-Pad9)") (class "Default")
      (node (ref "J32") (pin "9") (pinfunction "9_9") (pintype "passive"))
      (node (ref "R330") (pin "4") (pinfunction "4_4") (pintype "passive"))
    )
    (net (code "92") (name "Net-(J32-Pad10)") (class "Default")
      (node (ref "J32") (pin "10") (pinfunction "10_10") (pintype "passive"))
      (node (ref "R330") (pin "2") (pinfunction "2_2") (pintype "passive"))
    )
    (net (code "93") (name "Net-(LED2-C)") (class "Default")
      (node (ref "LED2") (pin "K") (pinfunction "C_K") (pintype "power_in"))
      (node (ref "R337") (pin "2") (pinfunction "2_2") (pintype "passive"))
    )
    (net (code "94") (name "Net-(LED3-C)") (class "Default")
      (node (ref "LED3") (pin "K") (pinfunction "C_K") (pintype "power_in"))
      (node (ref "R340") (pin "2") (pinfunction "2_2") (pintype "passive"))
    )
    (net (code "95") (name "Net-(LED4-C)") (class "Default")
      (node (ref "LED4") (pin "K") (pinfunction "C_K") (pintype "power_in"))
      (node (ref "R341") (pin "2") (pinfunction "2_2") (pintype "passive"))
    )
    (net (code "96") (name "Net-(LED5-C)") (class "Default")
      (node (ref "LED5") (pin "K") (pinfunction "C_K") (pintype "power_in"))
      (node (ref "R343") (pin "2") (pinfunction "2_2") (pintype "passive"))
    )
    (net (code "97") (name "Net-(LED6-Pad3)") (class "Default")
      (node (ref "LED6") (pin "3") (pinfunction "3_3") (pintype "power_in"))
      (node (ref "R345") (pin "2") (pinfunction "2_2") (pintype "passive"))
    )
    (net (code "98") (name "Net-(LED6-Pad4)") (class "Default")
      (node (ref "LED6") (pin "4") (pinfunction "4_4") (pintype "power_in"))
      (node (ref "R346") (pin "2") (pinfunction "2_2") (pintype "passive"))
    )
    (net (code "99") (name "VCC1P5") (class "Default")
      (node (ref "C766") (pin "1") (pinfunction "1_1") (pintype "passive"))
      (node (ref "C767") (pin "1") (pinfunction "1_1") (pintype "passive"))
      (node (ref "C776") (pin "1") (pinfunction "1_1") (pintype "passive"))
      (node (ref "IC44") (pin "20") (pinfunction "VCC_20") (pintype "passive"))
      (node (ref "IC45") (pin "20") (pinfunction "VCC_20") (pintype "passive"))
      (node (ref "IC49") (pin "14") (pinfunction "VCCA_14") (pintype "passive"))
      (node (ref "IC49") (pin "15") (pinfunction "DIR1_15") (pintype "passive"))
      (node (ref "IC49") (pin "16") (pinfunction "DIR2_16") (pintype "passive"))
      (node (ref "IC49") (pin "6") (pinfunction "DIR4_6") (pintype "passive"))
      (node (ref "R331") (pin "1") (pinfunction "1_1") (pintype "passive"))
      (node (ref "R332") (pin "1") (pinfunction "1_1") (pintype "passive"))
      (node (ref "R333") (pin "1") (pinfunction "1_1") (pintype "passive"))
      (node (ref "R334") (pin "1") (pinfunction "1_1") (pintype "passive"))
      (node (ref "R348") (pin "1") (pinfunction "1_1") (pintype "passive"))
      (node (ref "R349") (pin "1") (pinfunction "1_1") (pintype "passive"))
      (node (ref "R352") (pin "2") (pinfunction "2_2") (pintype "passive"))
      (node (ref "R362") (pin "2") (pinfunction "2_2") (pintype "passive"))
      (node (ref "R363") (pin "2") (pinfunction "2_2") (pintype "passive"))
      (node (ref "VT17") (pin "G") (pinfunction "G_G") (pintype "passive"))
      (node (ref "VT18") (pin "G") (pinfunction "G_G") (pintype "passive"))
    )
    (net (code "100") (name "VCC3P0_BATT") (class "Default")
      (node (ref "IC50") (pin "14") (pinfunction "VBAT_14") (pintype "power_in"))
      (node (ref "R360") (pin "2") (pinfunction "2_2") (pintype "passive"))
    )
    (net (code "101") (name "VCC3P3") (class "Default")
      (node (ref "C762") (pin "1") (pinfunction "1_1") (pintype "passive"))
      (node (ref "C763") (pin "1") (pinfunction "1_1") (pintype "passive"))
      (node (ref "C770") (pin "1") (pinfunction "1_1") (pintype "passive"))
      (node (ref "C772") (pin "1") (pinfunction "1_1") (pintype "passive"))
      (node (ref "C777") (pin "1") (pinfunction "1_1") (pintype "passive"))
      (node (ref "C778") (pin "1") (pinfunction "1_1") (pintype "passive"))
      (node (ref "C781") (pin "1") (pinfunction "1_1") (pintype "passive"))
      (node (ref "IC44") (pin "1") (pinfunction "VCCA_1") (pintype "passive"))
      (node (ref "IC45") (pin "1") (pinfunction "VCCA_1") (pintype "passive"))
      (node (ref "IC46") (pin "8") (pinfunction "VCC_8") (pintype "passive"))
      (node (ref "IC47") (pin "8") (pinfunction "VCC_8") (pintype "passive"))
      (node (ref "IC49") (pin "13") (pinfunction "VCCB_13") (pintype "passive"))
      (node (ref "IC50") (pin "2") (pinfunction "VCC_2") (pintype "power_in"))
      (node (ref "IC51") (pin "8") (pinfunction "VCC_8") (pintype "passive"))
      (node (ref "LED2") (pin "A") (pinfunction "A_A") (pintype "power_in"))
      (node (ref "LED3") (pin "A") (pinfunction "A_A") (pintype "power_in"))
      (node (ref "LED4") (pin "A") (pinfunction "A_A") (pintype "power_in"))
      (node (ref "LED5") (pin "A") (pinfunction "A_A") (pintype "power_in"))
      (node (ref "LED6") (pin "1") (pinfunction "1_1") (pintype "power_in"))
      (node (ref "LED6") (pin "2") (pinfunction "2_2") (pintype "power_in"))
      (node (ref "R335") (pin "2") (pinfunction "2_2") (pintype "passive"))
      (node (ref "R336") (pin "2") (pinfunction "2_2") (pintype "passive"))
      (node (ref "R350") (pin "1") (pinfunction "1_1") (pintype "passive"))
      (node (ref "R351") (pin "1") (pinfunction "1_1") (pintype "passive"))
      (node (ref "R356") (pin "2") (pinfunction "2_2") (pintype "passive"))
      (node (ref "R357") (pin "2") (pinfunction "2_2") (pintype "passive"))
      (node (ref "R359") (pin "2") (pinfunction "2_2") (pintype "passive"))
    )
    (net (code "102") (name "VCC3P3_CLK") (class "Default")
      (node (ref "FR97") (pin "1") (pinfunction "1_1") (pintype "passive"))
    )
    (net (code "103") (name "VCC3P3_GNSS") (class "Default")
      (node (ref "C775") (pin "2") (pinfunction "2_2") (pintype "passive"))
      (node (ref "C779") (pin "2") (pinfunction "2_2") (pintype "passive"))
      (node (ref "C780") (pin "2") (pinfunction "2_2") (pintype "passive"))
      (node (ref "FR97") (pin "2") (pinfunction "2_2") (pintype "passive"))
      (node (ref "IC48") (pin "15") (pinfunction "VCC_15") (pintype "power_in"))
      (node (ref "R354") (pin "1") (pinfunction "1_1") (pintype "passive"))
      (node (ref "R361") (pin "2") (pinfunction "2_2") (pintype "passive"))
    )
    (net (code "104") (name "VCC5P0") (class "Default")
      (node (ref "R339") (pin "2") (pinfunction "2_2") (pintype "passive"))
    )
    (net (code "105") (name "VCC12P0") (class "Default")
      (node (ref "R338") (pin "2") (pinfunction "2_2") (pintype "passive"))
    )
    (net (code "106") (name "unconnected-(IC48-E2-Pad11)") (class "Default")
      (node (ref "IC48") (pin "11") (pinfunction "E2_11") (pintype "passive+no_connect"))
    )
    (net (code "107") (name "unconnected-(IC48-E3-Pad12)") (class "Default")
      (node (ref "IC48") (pin "12") (pinfunction "E3_12") (pintype "passive+no_connect"))
    )
    (net (code "108") (name "unconnected-(IC48-HW_R-Pad7)") (class "Default")
      (node (ref "IC48") (pin "7") (pinfunction "HW_R_7") (pintype "input+no_connect"))
    )
    (net (code "109") (name "unconnected-(IC48-HW_S-Pad8)") (class "Default")
      (node (ref "IC48") (pin "8") (pinfunction "HW_S_8") (pintype "input+no_connect"))
    )
    (net (code "110") (name "unconnected-(IC50A-~{RST}-Pad4)") (class "Default")
      (node (ref "IC50") (pin "4") (pinfunction "~{RST}_4") (pintype "bidirectional+no_connect"))
    )
    (net (code "111") (name "unconnected-(IC50B-NC-Pad5)") (class "Default")
      (node (ref "IC50") (pin "5") (pinfunction "NC_5") (pintype "passive+no_connect"))
    )
    (net (code "112") (name "unconnected-(IC50B-NC-Pad6)") (class "Default")
      (node (ref "IC50") (pin "6") (pinfunction "NC_6") (pintype "passive+no_connect"))
    )
    (net (code "113") (name "unconnected-(IC50B-NC-Pad7)") (class "Default")
      (node (ref "IC50") (pin "7") (pinfunction "NC_7") (pintype "passive+no_connect"))
    )
    (net (code "114") (name "unconnected-(IC50B-NC-Pad8)") (class "Default")
      (node (ref "IC50") (pin "8") (pinfunction "NC_8") (pintype "passive+no_connect"))
    )
    (net (code "115") (name "unconnected-(IC50B-NC-Pad9)") (class "Default")
      (node (ref "IC50") (pin "9") (pinfunction "NC_9") (pintype "passive+no_connect"))
    )
    (net (code "116") (name "unconnected-(IC50B-NC-Pad10)") (class "Default")
      (node (ref "IC50") (pin "10") (pinfunction "NC_10") (pintype "passive+no_connect"))
    )
    (net (code "117") (name "unconnected-(IC50B-NC-Pad11)") (class "Default")
      (node (ref "IC50") (pin "11") (pinfunction "NC_11") (pintype "passive+no_connect"))
    )
    (net (code "118") (name "unconnected-(IC50B-NC-Pad12)") (class "Default")
      (node (ref "IC50") (pin "12") (pinfunction "NC_12") (pintype "passive+no_connect"))
    )
  )
)
